# Mikrobus-PIC32MX.net
KiCad netlist of a schematic drawn in EAGLE
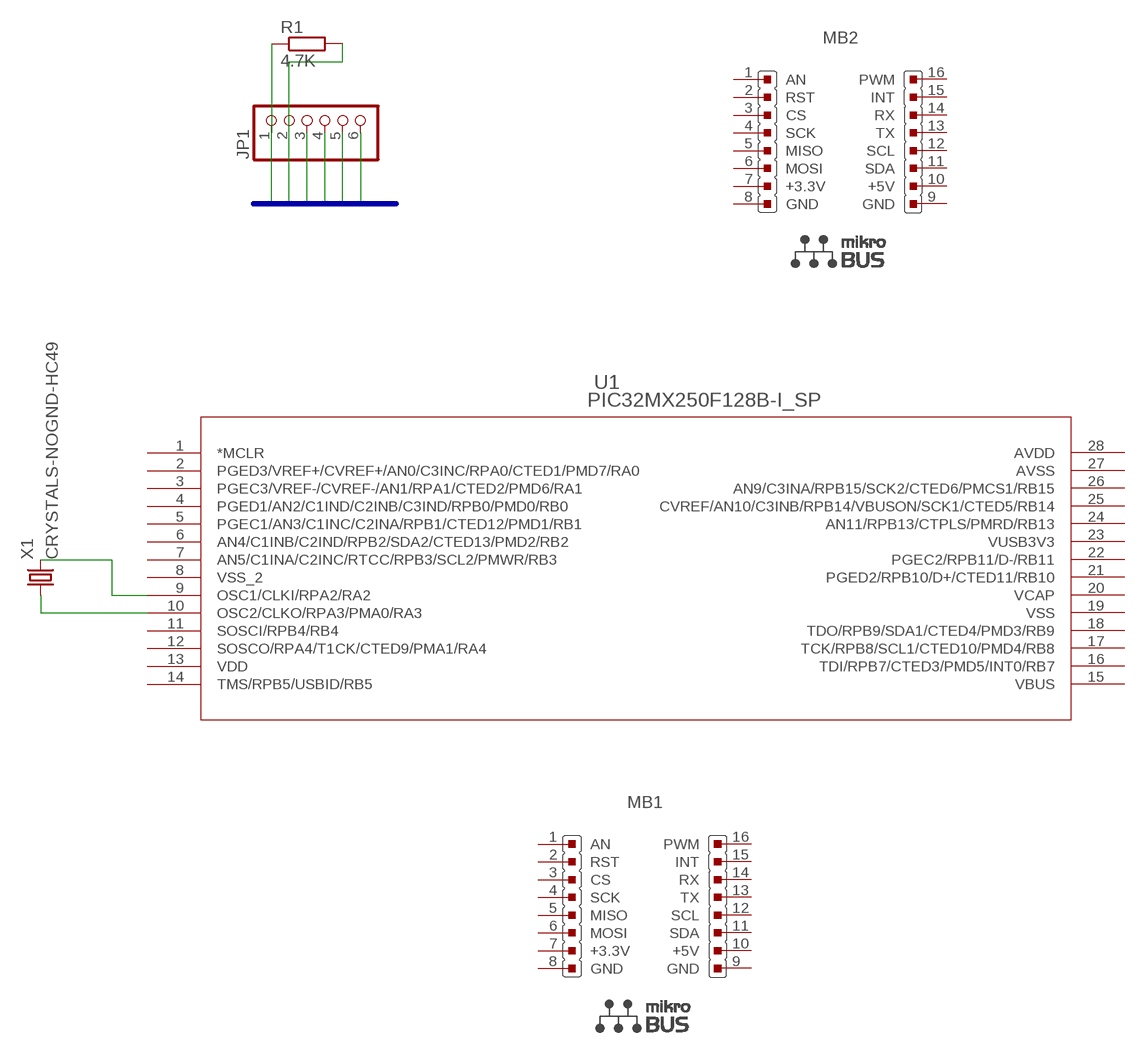
[diagram p0: schematic, sheet 1]

(export (version "E")
  (design (tool "Eeschema 10.0.6"))
  (components
    (comp (ref "JP1")
      (value "PINHD-1X6")
      (footprint "eagle-import:1X06")
      (libsource (lib "eagle-import") (part "PINHD-1X6"))
    )
    (comp (ref "MB1")
      (value "MIKROBUS")
      (footprint "eagle-import:MIKROBUS")
      (libsource (lib "eagle-import") (part "MIKROBUS"))
    )
    (comp (ref "MB2")
      (value "MIKROBUS")
      (footprint "eagle-import:MIKROBUS")
      (libsource (lib "eagle-import") (part "MIKROBUS"))
    )
    (comp (ref "R1")
      (value "4.7K")
      (footprint "eagle-import:0204_5")
      (libsource (lib "eagle-import") (part "R-EU_0204/5"))
    )
    (comp (ref "U1")
      (value "PIC32MX250F128B-I_SP")
      (footprint "eagle-import:SPDIP28_300MC")
      (libsource (lib "eagle-import") (part "PIC32MX250F128B-I_SP"))
    )
    (comp (ref "X1")
      (value "CRYSTALS-NOGND-HC49")
      (footprint "eagle-import:HC49")
      (libsource (lib "eagle-import") (part "CRYSTALS-NOGND-HC49"))
    )
  )
  (nets
    (net (code "1") (name "/AVDD") (class "Default")
      (node (ref "U1") (pin "28") (pinfunction "AVDD_28") (pintype "power_in"))
    )
    (net (code "2") (name "/AVSS") (class "Default")
      (node (ref "U1") (pin "27") (pinfunction "AVSS_27") (pintype "power_in"))
    )
    (net (code "3") (name "/VBUS") (class "Default")
      (node (ref "U1") (pin "15") (pinfunction "VBUS_15") (pintype "power_in"))
    )
    (net (code "4") (name "/VCAP") (class "Default")
      (node (ref "U1") (pin "20") (pinfunction "VCAP_20") (pintype "power_in"))
    )
    (net (code "5") (name "/VDD") (class "Default")
      (node (ref "U1") (pin "13") (pinfunction "VDD_13") (pintype "power_in"))
    )
    (net (code "6") (name "/VSS") (class "Default")
      (node (ref "U1") (pin "19") (pinfunction "VSS_19") (pintype "power_in"))
    )
    (net (code "7") (name "/VSS_2") (class "Default")
      (node (ref "U1") (pin "8") (pinfunction "VSS_2_8") (pintype "power_in"))
    )
    (net (code "8") (name "/VUSB3V3") (class "Default")
      (node (ref "U1") (pin "23") (pinfunction "VUSB3V3_23") (pintype "power_in"))
    )
    (net (code "9") (name "Net-(JP1-Pad1)") (class "Default")
      (node (ref "JP1") (pin "1") (pinfunction "1_1") (pintype "passive"))
      (node (ref "R1") (pin "1") (pinfunction "1_1") (pintype "passive"))
    )
    (net (code "10") (name "Net-(JP1-Pad2)") (class "Default")
      (node (ref "JP1") (pin "2") (pinfunction "2_2") (pintype "passive"))
      (node (ref "R1") (pin "2") (pinfunction "2_2") (pintype "passive"))
    )
    (net (code "11") (name "Net-(U1-OSC1{slash}CLKI{slash}RPA2{slash}RA2)") (class "Default")
      (node (ref "U1") (pin "9") (pinfunction "OSC1/CLKI/RPA2/RA2_9") (pintype "bidirectional"))
      (node (ref "X1") (pin "2") (pinfunction "2_2") (pintype "passive"))
    )
    (net (code "12") (name "Net-(U1-OSC2{slash}CLKO{slash}RPA3{slash}PMA0{slash}RA3)") (class "Default")
      (node (ref "U1") (pin "10") (pinfunction "OSC2/CLKO/RPA3/PMA0/RA3_10") (pintype "bidirectional"))
      (node (ref "X1") (pin "1") (pinfunction "1_1") (pintype "passive"))
    )
    (net (code "13") (name "unconnected-(JP1-Pad3)") (class "Default")
      (node (ref "JP1") (pin "3") (pinfunction "3_3") (pintype "passive"))
    )
    (net (code "14") (name "unconnected-(JP1-Pad4)") (class "Default")
      (node (ref "JP1") (pin "4") (pinfunction "4_4") (pintype "passive"))
    )
    (net (code "15") (name "unconnected-(JP1-Pad5)") (class "Default")
      (node (ref "JP1") (pin "5") (pinfunction "5_5") (pintype "passive"))
    )
    (net (code "16") (name "unconnected-(JP1-Pad6)") (class "Default")
      (node (ref "JP1") (pin "6") (pinfunction "6_6") (pintype "passive"))
    )
    (net (code "17") (name "unconnected-(MB1-+3.3V-Pad7)") (class "Default")
      (node (ref "MB1") (pin "7") (pinfunction "+3.3V_7") (pintype "passive"))
    )
    (net (code "18") (name "unconnected-(MB1-+5V-Pad10)") (class "Default")
      (node (ref "MB1") (pin "10") (pinfunction "+5V_10") (pintype "passive"))
    )
    (net (code "19") (name "unconnected-(MB1-AN-Pad1)") (class "Default")
      (node (ref "MB1") (pin "1") (pinfunction "AN_1") (pintype "bidirectional"))
    )
    (net (code "20") (name "unconnected-(MB1-CS-Pad3)") (class "Default")
      (node (ref "MB1") (pin "3") (pinfunction "CS_3") (pintype "bidirectional"))
    )
    (net (code "21") (name "unconnected-(MB1-GND-Pad8)") (class "Default")
      (node (ref "MB1") (pin "8") (pinfunction "GND_8") (pintype "passive"))
    )
    (net (code "22") (name "unconnected-(MB1-GND-Pad9)") (class "Default")
      (node (ref "MB1") (pin "9") (pinfunction "GND_9") (pintype "passive"))
    )
    (net (code "23") (name "unconnected-(MB1-INT-Pad15)") (class "Default")
      (node (ref "MB1") (pin "15") (pinfunction "INT_15") (pintype "bidirectional"))
    )
    (net (code "24") (name "unconnected-(MB1-MISO-Pad5)") (class "Default")
      (node (ref "MB1") (pin "5") (pinfunction "MISO_5") (pintype "bidirectional"))
    )
    (net (code "25") (name "unconnected-(MB1-MOSI-Pad6)") (class "Default")
      (node (ref "MB1") (pin "6") (pinfunction "MOSI_6") (pintype "bidirectional"))
    )
    (net (code "26") (name "unconnected-(MB1-PWM-Pad16)") (class "Default")
      (node (ref "MB1") (pin "16") (pinfunction "PWM_16") (pintype "bidirectional"))
    )
    (net (code "27") (name "unconnected-(MB1-RST-Pad2)") (class "Default")
      (node (ref "MB1") (pin "2") (pinfunction "RST_2") (pintype "bidirectional"))
    )
    (net (code "28") (name "unconnected-(MB1-RX-Pad14)") (class "Default")
      (node (ref "MB1") (pin "14") (pinfunction "RX_14") (pintype "bidirectional"))
    )
    (net (code "29") (name "unconnected-(MB1-SCK-Pad4)") (class "Default")
      (node (ref "MB1") (pin "4") (pinfunction "SCK_4") (pintype "bidirectional"))
    )
    (net (code "30") (name "unconnected-(MB1-SCL-Pad12)") (class "Default")
      (node (ref "MB1") (pin "12") (pinfunction "SCL_12") (pintype "bidirectional"))
    )
    (net (code "31") (name "unconnected-(MB1-SDA-Pad11)") (class "Default")
      (node (ref "MB1") (pin "11") (pinfunction "SDA_11") (pintype "bidirectional"))
    )
    (net (code "32") (name "unconnected-(MB1-TX-Pad13)") (class "Default")
      (node (ref "MB1") (pin "13") (pinfunction "TX_13") (pintype "bidirectional"))
    )
    (net (code "33") (name "unconnected-(MB2-+3.3V-Pad7)") (class "Default")
      (node (ref "MB2") (pin "7") (pinfunction "+3.3V_7") (pintype "passive"))
    )
    (net (code "34") (name "unconnected-(MB2-+5V-Pad10)") (class "Default")
      (node (ref "MB2") (pin "10") (pinfunction "+5V_10") (pintype "passive"))
    )
    (net (code "35") (name "unconnected-(MB2-AN-Pad1)") (class "Default")
      (node (ref "MB2") (pin "1") (pinfunction "AN_1") (pintype "bidirectional"))
    )
    (net (code "36") (name "unconnected-(MB2-CS-Pad3)") (class "Default")
      (node (ref "MB2") (pin "3") (pinfunction "CS_3") (pintype "bidirectional"))
    )
    (net (code "37") (name "unconnected-(MB2-GND-Pad8)") (class "Default")
      (node (ref "MB2") (pin "8") (pinfunction "GND_8") (pintype "passive"))
    )
    (net (code "38") (name "unconnected-(MB2-GND-Pad9)") (class "Default")
      (node (ref "MB2") (pin "9") (pinfunction "GND_9") (pintype "passive"))
    )
    (net (code "39") (name "unconnected-(MB2-INT-Pad15)") (class "Default")
      (node (ref "MB2") (pin "15") (pinfunction "INT_15") (pintype "bidirectional"))
    )
    (net (code "40") (name "unconnected-(MB2-MISO-Pad5)") (class "Default")
      (node (ref "MB2") (pin "5") (pinfunction "MISO_5") (pintype "bidirectional"))
    )
    (net (code "41") (name "unconnected-(MB2-MOSI-Pad6)") (class "Default")
      (node (ref "MB2") (pin "6") (pinfunction "MOSI_6") (pintype "bidirectional"))
    )
    (net (code "42") (name "unconnected-(MB2-PWM-Pad16)") (class "Default")
      (node (ref "MB2") (pin "16") (pinfunction "PWM_16") (pintype "bidirectional"))
    )
    (net (code "43") (name "unconnected-(MB2-RST-Pad2)") (class "Default")
      (node (ref "MB2") (pin "2") (pinfunction "RST_2") (pintype "bidirectional"))
    )
    (net (code "44") (name "unconnected-(MB2-RX-Pad14)") (class "Default")
      (node (ref "MB2") (pin "14") (pinfunction "RX_14") (pintype "bidirectional"))
    )
    (net (code "45") (name "unconnected-(MB2-SCK-Pad4)") (class "Default")
      (node (ref "MB2") (pin "4") (pinfunction "SCK_4") (pintype "bidirectional"))
    )
    (net (code "46") (name "unconnected-(MB2-SCL-Pad12)") (class "Default")
      (node (ref "MB2") (pin "12") (pinfunction "SCL_12") (pintype "bidirectional"))
    )
    (net (code "47") (name "unconnected-(MB2-SDA-Pad11)") (class "Default")
      (node (ref "MB2") (pin "11") (pinfunction "SDA_11") (pintype "bidirectional"))
    )
    (net (code "48") (name "unconnected-(MB2-TX-Pad13)") (class "Default")
      (node (ref "MB2") (pin "13") (pinfunction "TX_13") (pintype "bidirectional"))
    )
    (net (code "49") (name "unconnected-(U1-*MCLR-Pad1)") (class "Default")
      (node (ref "U1") (pin "1") (pinfunction "*MCLR_1") (pintype "input"))
    )
    (net (code "50") (name "unconnected-(U1-AN4{slash}C1INB{slash}C2IND{slash}RPB2{slash}SDA2{slash}CTED13{slash}PMD2{slash}RB2-Pad6)") (class "Default")
      (node (ref "U1") (pin "6") (pinfunction "AN4/C1INB/C2IND/RPB2/SDA2/CTED13/PMD2/RB2_6") (pintype "bidirectional"))
    )
    (net (code "51") (name "unconnected-(U1-AN5{slash}C1INA{slash}C2INC{slash}RTCC{slash}RPB3{slash}SCL2{slash}PMWR{slash}RB3-Pad7)") (class "Default")
      (node (ref "U1") (pin "7") (pinfunction "AN5/C1INA/C2INC/RTCC/RPB3/SCL2/PMWR/RB3_7") (pintype "bidirectional"))
    )
    (net (code "52") (name "unconnected-(U1-AN9{slash}C3INA{slash}RPB15{slash}SCK2{slash}CTED6{slash}PMCS1{slash}RB15-Pad26)") (class "Default")
      (node (ref "U1") (pin "26") (pinfunction "AN9/C3INA/RPB15/SCK2/CTED6/PMCS1/RB15_26") (pintype "bidirectional"))
    )
    (net (code "53") (name "unconnected-(U1-AN11{slash}RPB13{slash}CTPLS{slash}PMRD{slash}RB13-Pad24)") (class "Default")
      (node (ref "U1") (pin "24") (pinfunction "AN11/RPB13/CTPLS/PMRD/RB13_24") (pintype "bidirectional"))
    )
    (net (code "54") (name "unconnected-(U1-CVREF{slash}AN10{slash}C3INB{slash}RPB14{slash}VBUSON{slash}SCK1{slash}CTED5{slash}RB14-Pad25)") (class "Default")
      (node (ref "U1") (pin "25") (pinfunction "CVREF/AN10/C3INB/RPB14/VBUSON/SCK1/CTED5/RB14_25") (pintype "bidirectional"))
    )
    (net (code "55") (name "unconnected-(U1-PGEC1{slash}AN3{slash}C1INC{slash}C2INA{slash}RPB1{slash}CTED12{slash}PMD1{slash}RB1-Pad5)") (class "Default")
      (node (ref "U1") (pin "5") (pinfunction "PGEC1/AN3/C1INC/C2INA/RPB1/CTED12/PMD1/RB1_5") (pintype "bidirectional"))
    )
    (net (code "56") (name "unconnected-(U1-PGEC2{slash}RPB11{slash}D-{slash}RB11-Pad22)") (class "Default")
      (node (ref "U1") (pin "22") (pinfunction "PGEC2/RPB11/D-/RB11_22") (pintype "bidirectional"))
    )
    (net (code "57") (name "unconnected-(U1-PGEC3{slash}VREF-{slash}CVREF-{slash}AN1{slash}RPA1{slash}CTED2{slash}PMD6{slash}RA1-Pad3)") (class "Default")
      (node (ref "U1") (pin "3") (pinfunction "PGEC3/VREF-/CVREF-/AN1/RPA1/CTED2/PMD6/RA1_3") (pintype "bidirectional"))
    )
    (net (code "58") (name "unconnected-(U1-PGED1{slash}AN2{slash}C1IND{slash}C2INB{slash}C3IND{slash}RPB0{slash}PMD0{slash}RB0-Pad4)") (class "Default")
      (node (ref "U1") (pin "4") (pinfunction "PGED1/AN2/C1IND/C2INB/C3IND/RPB0/PMD0/RB0_4") (pintype "bidirectional"))
    )
    (net (code "59") (name "unconnected-(U1-PGED2{slash}RPB10{slash}D+{slash}CTED11{slash}RB10-Pad21)") (class "Default")
      (node (ref "U1") (pin "21") (pinfunction "PGED2/RPB10/D+/CTED11/RB10_21") (pintype "bidirectional"))
    )
    (net (code "60") (name "unconnected-(U1-PGED3{slash}VREF+{slash}CVREF+{slash}AN0{slash}C3INC{slash}RPA0{slash}CTED1{slash}PMD7{slash}RA0-Pad2)") (class "Default")
      (node (ref "U1") (pin "2") (pinfunction "PGED3/VREF+/CVREF+/AN0/C3INC/RPA0/CTED1/PMD7/RA0_2") (pintype "bidirectional"))
    )
    (net (code "61") (name "unconnected-(U1-SOSCI{slash}RPB4{slash}RB4-Pad11)") (class "Default")
      (node (ref "U1") (pin "11") (pinfunction "SOSCI/RPB4/RB4_11") (pintype "bidirectional"))
    )
    (net (code "62") (name "unconnected-(U1-SOSCO{slash}RPA4{slash}T1CK{slash}CTED9{slash}PMA1{slash}RA4-Pad12)") (class "Default")
      (node (ref "U1") (pin "12") (pinfunction "SOSCO/RPA4/T1CK/CTED9/PMA1/RA4_12") (pintype "bidirectional"))
    )
    (net (code "63") (name "unconnected-(U1-TCK{slash}RPB8{slash}SCL1{slash}CTED10{slash}PMD4{slash}RB8-Pad17)") (class "Default")
      (node (ref "U1") (pin "17") (pinfunction "TCK/RPB8/SCL1/CTED10/PMD4/RB8_17") (pintype "bidirectional"))
    )
    (net (code "64") (name "unconnected-(U1-TDI{slash}RPB7{slash}CTED3{slash}PMD5{slash}INT0{slash}RB7-Pad16)") (class "Default")
      (node (ref "U1") (pin "16") (pinfunction "TDI/RPB7/CTED3/PMD5/INT0/RB7_16") (pintype "bidirectional"))
    )
    (net (code "65") (name "unconnected-(U1-TDO{slash}RPB9{slash}SDA1{slash}CTED4{slash}PMD3{slash}RB9-Pad18)") (class "Default")
      (node (ref "U1") (pin "18") (pinfunction "TDO/RPB9/SDA1/CTED4/PMD3/RB9_18") (pintype "bidirectional"))
    )
    (net (code "66") (name "unconnected-(U1-TMS{slash}RPB5{slash}USBID{slash}RB5-Pad14)") (class "Default")
      (node (ref "U1") (pin "14") (pinfunction "TMS/RPB5/USBID/RB5_14") (pintype "bidirectional"))
    )
  )
)
